# ADAU1452KCPZ.net
KiCad netlist of a schematic drawn in Altium Designer
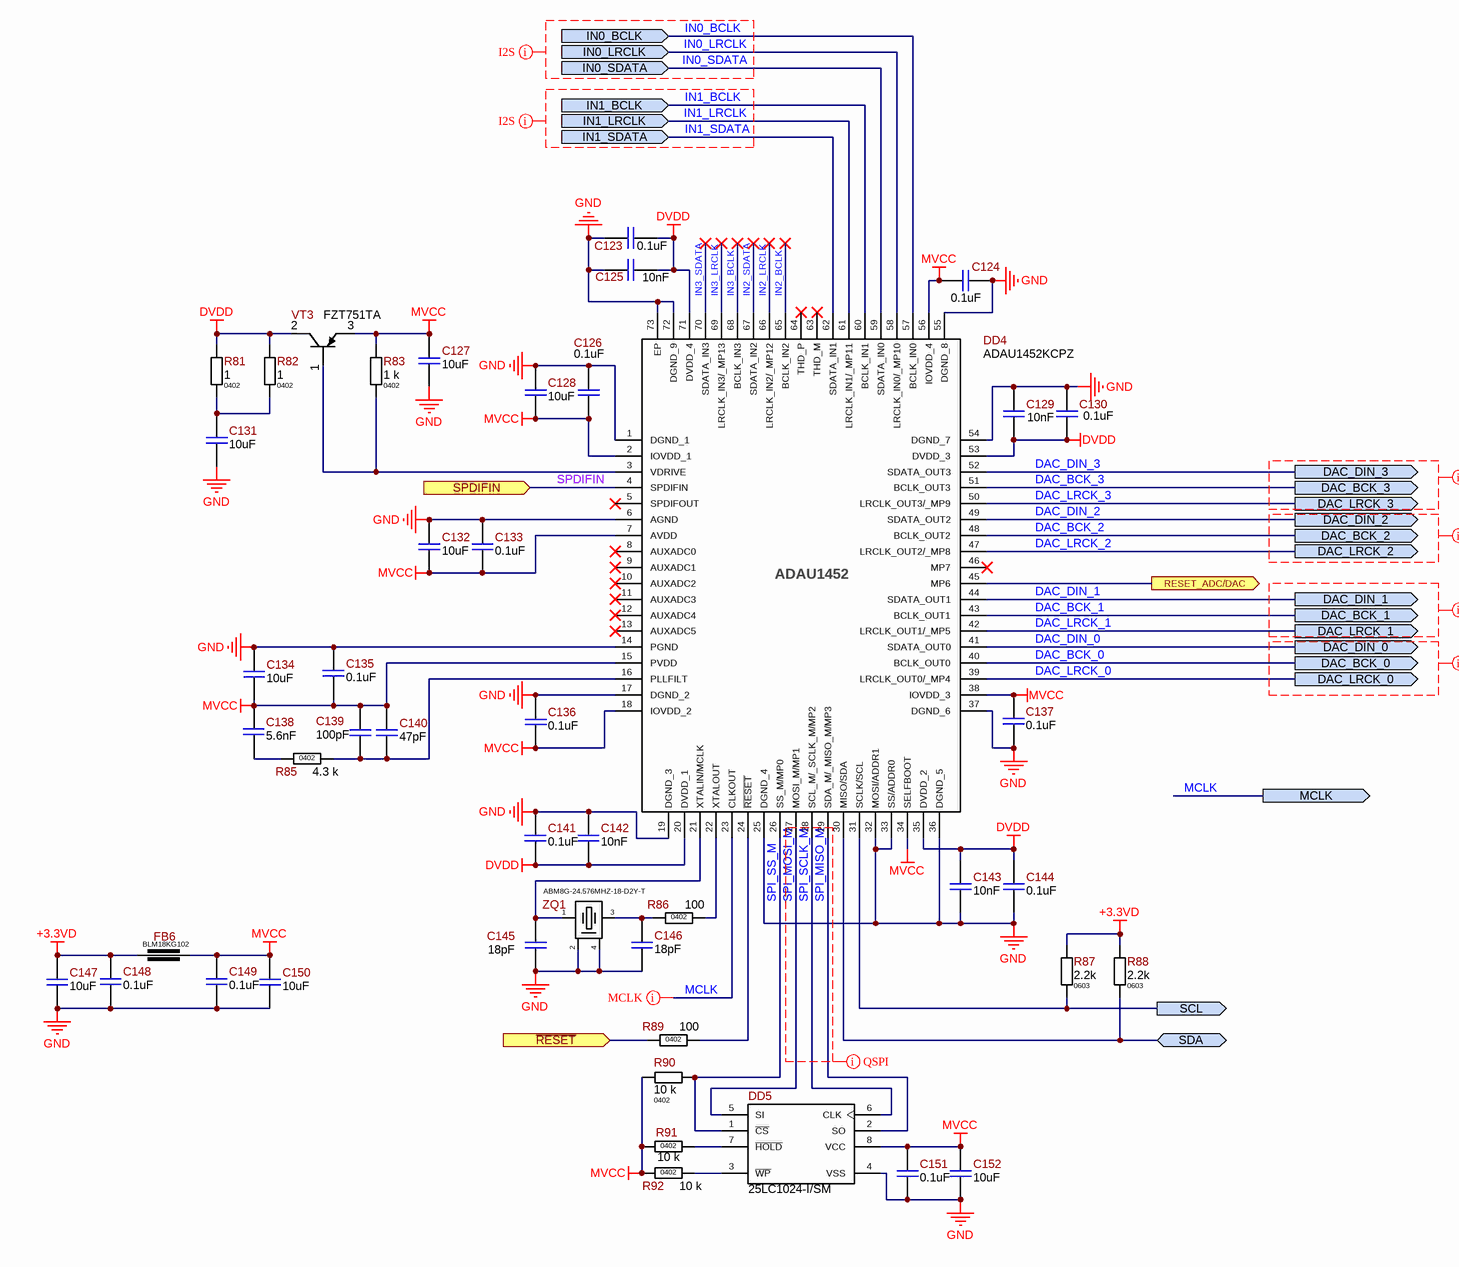
[diagram p0: ADAU1452KCPZ.SchDoc]

(export (version "E")
  (design (tool "Eeschema 10.0.6"))
  (components
    (comp (ref "C123")
      (value "0.1uF")
      (footprint "C0402(1005)")
      (description "CAP CER 0.1UF 25V X7R 0603")
      (fields (field (name "PART NUMBER") "0.1uF  25V C0403") (field (name "TOLERANCE") "±10%"))
      (libsource (lib "Database") (part "Capacitor_Ceramic"))
    )
    (comp (ref "C124")
      (value "0.1uF")
      (footprint "C0402(1005)")
      (description "CAP CER 0.1UF 25V X7R 0603")
      (fields (field (name "PART NUMBER") "0.1uF  25V C0403") (field (name "TOLERANCE") "±10%"))
      (libsource (lib "Database") (part "Capacitor_Ceramic"))
    )
    (comp (ref "C125")
      (value "10nF")
      (footprint "C0402(1005)")
      (description "CAP CER 10NF 50V NP0 0603")
      (fields (field (name "PART NUMBER") "10nF  50V C0402") (field (name "TOLERANCE") "±0.25pF"))
      (libsource (lib "Database") (part "Capacitor_Ceramic"))
    )
    (comp (ref "C126")
      (value "0.1uF")
      (footprint "C0402(1005)")
      (description "CAP CER 0.1UF 25V X7R 0603")
      (fields (field (name "PART NUMBER") "0.1uF  25V C0403") (field (name "TOLERANCE") "±10%"))
      (libsource (lib "Database") (part "Capacitor_Ceramic"))
    )
    (comp (ref "C127")
      (value "10uF")
      (footprint "C0402(1005)")
      (description "CAP CER 10UF 6.3V X6S 0402")
      (fields (field (name "PART NUMBER") "10uF  6.3V C0402") (field (name "TOLERANCE") "±20%"))
      (libsource (lib "Database") (part "Capacitor_Ceramic"))
    )
    (comp (ref "C128")
      (value "10uF")
      (footprint "C0402(1005)")
      (description "CAP CER 10UF 6.3V X6S 0402")
      (fields (field (name "PART NUMBER") "10uF  6.3V C0402") (field (name "TOLERANCE") "±20%"))
      (libsource (lib "Database") (part "Capacitor_Ceramic"))
    )
    (comp (ref "C129")
      (value "10nF")
      (footprint "C0402(1005)")
      (description "CAP CER 10NF 50V NP0 0603")
      (fields (field (name "PART NUMBER") "10nF  50V C0402") (field (name "TOLERANCE") "±0.25pF"))
      (libsource (lib "Database") (part "Capacitor_Ceramic"))
    )
    (comp (ref "C130")
      (value "0.1uF")
      (footprint "C0402(1005)")
      (description "CAP CER 0.1UF 25V X7R 0603")
      (fields (field (name "PART NUMBER") "0.1uF  25V C0403") (field (name "TOLERANCE") "±10%"))
      (libsource (lib "Database") (part "Capacitor_Ceramic"))
    )
    (comp (ref "C131")
      (value "10uF")
      (footprint "C0402(1005)")
      (description "CAP CER 10UF 6.3V X6S 0402")
      (fields (field (name "PART NUMBER") "10uF  6.3V C0402") (field (name "TOLERANCE") "±20%"))
      (libsource (lib "Database") (part "Capacitor_Ceramic"))
    )
    (comp (ref "C132")
      (value "10uF")
      (footprint "C0402(1005)")
      (description "CAP CER 10UF 6.3V X6S 0402")
      (fields (field (name "PART NUMBER") "10uF  6.3V C0402") (field (name "TOLERANCE") "±20%"))
      (libsource (lib "Database") (part "Capacitor_Ceramic"))
    )
    (comp (ref "C133")
      (value "0.1uF")
      (footprint "C0402(1005)")
      (description "CAP CER 0.1UF 25V X7R 0603")
      (fields (field (name "PART NUMBER") "0.1uF  25V C0403") (field (name "TOLERANCE") "±10%"))
      (libsource (lib "Database") (part "Capacitor_Ceramic"))
    )
    (comp (ref "C134")
      (value "10uF")
      (footprint "C0402(1005)")
      (description "CAP CER 10UF 6.3V X6S 0402")
      (fields (field (name "PART NUMBER") "10uF  6.3V C0402") (field (name "TOLERANCE") "±20%"))
      (libsource (lib "Database") (part "Capacitor_Ceramic"))
    )
    (comp (ref "C135")
      (value "0.1uF")
      (footprint "C0402(1005)")
      (description "CAP CER 0.1UF 25V X7R 0603")
      (fields (field (name "PART NUMBER") "0.1uF  25V C0403") (field (name "TOLERANCE") "±10%"))
      (libsource (lib "Database") (part "Capacitor_Ceramic"))
    )
    (comp (ref "C136")
      (value "0.1uF")
      (footprint "C0402(1005)")
      (description "CAP CER 0.1UF 25V X7R 0603")
      (fields (field (name "PART NUMBER") "0.1uF  25V C0403") (field (name "TOLERANCE") "±10%"))
      (libsource (lib "Database") (part "Capacitor_Ceramic"))
    )
    (comp (ref "C137")
      (value "0.1uF")
      (footprint "C0402(1005)")
      (description "CAP CER 0.1UF 25V X7R 0603")
      (fields (field (name "PART NUMBER") "0.1uF  25V C0403") (field (name "TOLERANCE") "±10%"))
      (libsource (lib "Database") (part "Capacitor_Ceramic"))
    )
    (comp (ref "C138")
      (value "5.6nF")
      (footprint "C0402(1005)")
      (description "CAP CER 5.6NF 50V NP0 0603")
      (fields (field (name "PART NUMBER") "5.6nF  50V C0402") (field (name "TOLERANCE") "±0.25pF"))
      (libsource (lib "Database") (part "Capacitor_Ceramic"))
    )
    (comp (ref "C139")
      (value "100pF")
      (footprint "C0402(1005)")
      (description "CAP CER 100PF 50V NP0 0603")
      (fields (field (name "PART NUMBER") "100pF  50V C0402") (field (name "TOLERANCE") "±0.25pF"))
      (libsource (lib "Database") (part "Capacitor_Ceramic"))
    )
    (comp (ref "C140")
      (value "47pF")
      (footprint "C0402(1005)")
      (description "CAP CER 47PF 50V NP0 0603")
      (fields (field (name "PART NUMBER") "47pF  50V C0402") (field (name "TOLERANCE") "±0.25pF"))
      (libsource (lib "Database") (part "Capacitor_Ceramic"))
    )
    (comp (ref "C141")
      (value "0.1uF")
      (footprint "C0402(1005)")
      (description "CAP CER 0.1UF 25V X7R 0603")
      (fields (field (name "PART NUMBER") "0.1uF  25V C0403") (field (name "TOLERANCE") "±10%"))
      (libsource (lib "Database") (part "Capacitor_Ceramic"))
    )
    (comp (ref "C142")
      (value "10nF")
      (footprint "C0402(1005)")
      (description "CAP CER 10NF 50V NP0 0603")
      (fields (field (name "PART NUMBER") "10nF  50V C0402") (field (name "TOLERANCE") "±0.25pF"))
      (libsource (lib "Database") (part "Capacitor_Ceramic"))
    )
    (comp (ref "C143")
      (value "10nF")
      (footprint "C0402(1005)")
      (description "CAP CER 10NF 50V NP0 0603")
      (fields (field (name "PART NUMBER") "10nF  50V C0402") (field (name "TOLERANCE") "±0.25pF"))
      (libsource (lib "Database") (part "Capacitor_Ceramic"))
    )
    (comp (ref "C144")
      (value "0.1uF")
      (footprint "C0402(1005)")
      (description "CAP CER 0.1UF 25V X7R 0603")
      (fields (field (name "PART NUMBER") "0.1uF  25V C0403") (field (name "TOLERANCE") "±10%"))
      (libsource (lib "Database") (part "Capacitor_Ceramic"))
    )
    (comp (ref "C145")
      (value "18pF")
      (footprint "C0402(1005)")
      (description "CAP CER 18PF 50V NP0 0603")
      (fields (field (name "PART NUMBER") "18pF  50V C0402") (field (name "TOLERANCE") "±0.25pF"))
      (libsource (lib "Database") (part "Capacitor_Ceramic"))
    )
    (comp (ref "C146")
      (value "18pF")
      (footprint "C0402(1005)")
      (description "CAP CER 18PF 50V NP0 0603")
      (fields (field (name "PART NUMBER") "18pF  50V C0402") (field (name "TOLERANCE") "±0.25pF"))
      (libsource (lib "Database") (part "Capacitor_Ceramic"))
    )
    (comp (ref "C147")
      (value "10uF")
      (footprint "C0402(1005)")
      (description "CAP CER 10UF 6.3V X6S 0402")
      (fields (field (name "PART NUMBER") "10uF  6.3V C0402") (field (name "TOLERANCE") "±20%"))
      (libsource (lib "Database") (part "Capacitor_Ceramic"))
    )
    (comp (ref "C148")
      (value "0.1uF")
      (footprint "C0402(1005)")
      (description "CAP CER 0.1UF 25V X7R 0603")
      (fields (field (name "PART NUMBER") "0.1uF  25V C0403") (field (name "TOLERANCE") "±10%"))
      (libsource (lib "Database") (part "Capacitor_Ceramic"))
    )
    (comp (ref "C149")
      (value "0.1uF")
      (footprint "C0402(1005)")
      (description "CAP CER 0.1UF 25V X7R 0603")
      (fields (field (name "PART NUMBER") "0.1uF  25V C0403") (field (name "TOLERANCE") "±10%"))
      (libsource (lib "Database") (part "Capacitor_Ceramic"))
    )
    (comp (ref "C150")
      (value "10uF")
      (footprint "C0402(1005)")
      (description "CAP CER 10UF 6.3V X6S 0402")
      (fields (field (name "PART NUMBER") "10uF  6.3V C0402") (field (name "TOLERANCE") "±20%"))
      (libsource (lib "Database") (part "Capacitor_Ceramic"))
    )
    (comp (ref "C151")
      (value "0.1uF")
      (footprint "C0402(1005)")
      (description "CAP CER 0.1UF 25V X7R 0603")
      (fields (field (name "PART NUMBER") "0.1uF  25V C0403") (field (name "TOLERANCE") "±10%"))
      (libsource (lib "Database") (part "Capacitor_Ceramic"))
    )
    (comp (ref "C152")
      (value "10uF")
      (footprint "C0402(1005)")
      (description "CAP CER 10UF 6.3V X6S 0402")
      (fields (field (name "PART NUMBER") "10uF  6.3V C0402") (field (name "TOLERANCE") "±20%"))
      (libsource (lib "Database") (part "Capacitor_Ceramic"))
    )
    (comp (ref "DD4")
      (value "ADAU1452KCPZ")
      (footprint "QFN50P1000X1000X100-73N-D")
      (description "300 MHZ 32BIT SIGMADSP AUDIO PRO")
      (fields (field (name "MANUFACTURER") "Analog Devices Inc."))
      (libsource (lib "Database") (part "ADAU1452KCPZ"))
    )
    (comp (ref "DD5")
      (value "25LC1024-I/SM")
      (footprint "SOIC8")
      (description "EEPROM Memory IC 1Mbit SPI 20 MHz 8-SOIJ")
      (fields (field (name "MANUFACTURER") "Microchip Technology"))
      (libsource (lib "Database") (part "W25Q32"))
    )
    (comp (ref "FB6")
      (value "BLM18KG102")
      (footprint "BLM18(0603)")
      (description "FERRITE BEAD 1 KOHM 0603 1LN")
      (fields
        (field (name "TOLERANCE") "±25%")
        (field (name "MANUFACTURER") "Murata Electronics North America")
      )
      (libsource (lib "Database") (part "FB"))
    )
    (comp (ref "R81")
      (value "1")
      (footprint "R0402")
      (description "RES SMD 1 OHM  ±1% 1/16W 0402")
      (fields
        (field (name "PACKAGE/CASE") "0402")
        (field (name "PART NUMBER") "1  R0402")
        (field (name "TOLERANCE") "±1%")
      )
      (libsource (lib "Database") (part "R0402"))
    )
    (comp (ref "R82")
      (value "1")
      (footprint "R0402")
      (description "RES SMD 1 OHM  ±1% 1/16W 0402")
      (fields
        (field (name "PACKAGE/CASE") "0402")
        (field (name "PART NUMBER") "1  R0402")
        (field (name "TOLERANCE") "±1%")
      )
      (libsource (lib "Database") (part "R0402"))
    )
    (comp (ref "R83")
      (value "1 k")
      (footprint "R0402")
      (description "RES SMD 1 k OHM  ±1% 1/16W 0402")
      (fields
        (field (name "PACKAGE/CASE") "0402")
        (field (name "PART NUMBER") "1 k  R0402")
        (field (name "TOLERANCE") "±1%")
      )
      (libsource (lib "Database") (part "R0402"))
    )
    (comp (ref "R85")
      (value "4.3 k")
      (footprint "R0402")
      (description "RES SMD 4.3 k OHM  ±1% 1/16W 0402")
      (fields
        (field (name "PACKAGE/CASE") "0402")
        (field (name "PART NUMBER") "4.3 k  R0402")
        (field (name "TOLERANCE") "±1%")
      )
      (libsource (lib "Database") (part "R0402"))
    )
    (comp (ref "R86")
      (value "100")
      (footprint "R0402")
      (description "RES SMD 100 OHM  ±1% 1/16W 0402")
      (fields
        (field (name "PACKAGE/CASE") "0402")
        (field (name "PART NUMBER") "100  R0402")
        (field (name "TOLERANCE") "±1%")
      )
      (libsource (lib "Database") (part "R0402"))
    )
    (comp (ref "R87")
      (value "2.2k")
      (footprint "R0603")
      (description "RES SMD 10 k OHM  ±1% 1/10W 0603")
      (fields
        (field (name "PACKAGE/CASE") "0603")
        (field (name "PART NUMBER") "10 k  R0603")
        (field (name "TOLERANCE") "±1%")
      )
      (libsource (lib "Database") (part "R0603"))
    )
    (comp (ref "R88")
      (value "2.2k")
      (footprint "R0603")
      (description "RES SMD 10 k OHM  ±1% 1/10W 0603")
      (fields
        (field (name "PACKAGE/CASE") "0603")
        (field (name "PART NUMBER") "10 k  R0603")
        (field (name "TOLERANCE") "±1%")
      )
      (libsource (lib "Database") (part "R0603"))
    )
    (comp (ref "R89")
      (value "100")
      (footprint "R0402")
      (description "RES SMD 100 OHM  ±1% 1/16W 0402")
      (fields
        (field (name "PACKAGE/CASE") "0402")
        (field (name "PART NUMBER") "100  R0402")
        (field (name "TOLERANCE") "±1%")
      )
      (libsource (lib "Database") (part "R0402"))
    )
    (comp (ref "R90")
      (value "10 k")
      (footprint "R0402")
      (description "RES SMD 10 k OHM  ±1% 1/16W 0402")
      (fields
        (field (name "PACKAGE/CASE") "0402")
        (field (name "PART NUMBER") "10 k  R0402")
        (field (name "TOLERANCE") "±1%")
      )
      (libsource (lib "Database") (part "R0402"))
    )
    (comp (ref "R91")
      (value "10 k")
      (footprint "R0402")
      (description "RES SMD 10 k OHM  ±1% 1/16W 0402")
      (fields
        (field (name "PACKAGE/CASE") "0402")
        (field (name "PART NUMBER") "10 k  R0402")
        (field (name "TOLERANCE") "±1%")
      )
      (libsource (lib "Database") (part "R0402"))
    )
    (comp (ref "R92")
      (value "10 k")
      (footprint "R0402")
      (description "RES SMD 10 k OHM  ±1% 1/16W 0402")
      (fields
        (field (name "PACKAGE/CASE") "0402")
        (field (name "PART NUMBER") "10 k  R0402")
        (field (name "TOLERANCE") "±1%")
      )
      (libsource (lib "Database") (part "R0402"))
    )
    (comp (ref "VT3")
      (value "FZT751TA")
      (footprint "SOT-223")
      (description "Bipolar (BJT) Transistor PNP 60 V 3 A 140MHz 2 W Surface Mount SOT-223-3")
      (fields (field (name "MANUFACTURER") "Diodes Incorporated"))
      (libsource (lib "Database") (part "FZT751TA"))
    )
    (comp (ref "ZQ1")
      (value "ABM8G-24.576MHZ-18-D2Y-T")
      (footprint "ABM8")
      (description "CRYSTAL 24.5760MHZ 18PF SMD")
      (fields (field (name "TOLERANCE") "±20ppm") (field (name "MANUFACTURER") "Abracon LLC"))
      (libsource (lib "Database") (part "Crystals_2"))
    )
  )
  (nets
    (net (code "1") (name "+3.3VD") (class "Default")
      (node (ref "C147") (pin "2") (pinfunction "2_2") (pintype "passive"))
      (node (ref "C148") (pin "1") (pinfunction "1_1") (pintype "passive"))
      (node (ref "FB6") (pin "1") (pintype "passive"))
      (node (ref "R87") (pin "1") (pinfunction "1_1") (pintype "passive"))
      (node (ref "R88") (pin "1") (pinfunction "1_1") (pintype "passive"))
    )
    (net (code "2") (name "/DAC_BCK_0") (class "Default")
      (node (ref "DD4") (pin "40") (pinfunction "BCLK_OUT0_40") (pintype "passive"))
    )
    (net (code "3") (name "/DAC_BCK_1") (class "Default")
      (node (ref "DD4") (pin "43") (pinfunction "BCLK_OUT1_43") (pintype "passive"))
    )
    (net (code "4") (name "/DAC_BCK_2") (class "Default")
      (node (ref "DD4") (pin "48") (pinfunction "BCLK_OUT2_48") (pintype "passive"))
    )
    (net (code "5") (name "/DAC_BCK_3") (class "Default")
      (node (ref "DD4") (pin "51") (pinfunction "BCLK_OUT3_51") (pintype "passive"))
    )
    (net (code "6") (name "/DAC_DIN_0") (class "Default")
      (node (ref "DD4") (pin "41") (pinfunction "SDATA_OUT0_41") (pintype "passive"))
    )
    (net (code "7") (name "/DAC_DIN_1") (class "Default")
      (node (ref "DD4") (pin "44") (pinfunction "SDATA_OUT1_44") (pintype "passive"))
    )
    (net (code "8") (name "/DAC_DIN_2") (class "Default")
      (node (ref "DD4") (pin "49") (pinfunction "SDATA_OUT2_49") (pintype "passive"))
    )
    (net (code "9") (name "/DAC_DIN_3") (class "Default")
      (node (ref "DD4") (pin "52") (pinfunction "SDATA_OUT3_52") (pintype "passive"))
    )
    (net (code "10") (name "/DAC_LRCK_0") (class "Default")
      (node (ref "DD4") (pin "39") (pinfunction "LRCLK_OUT0/_MP4_39") (pintype "passive"))
    )
    (net (code "11") (name "/DAC_LRCK_1") (class "Default")
      (node (ref "DD4") (pin "42") (pinfunction "LRCLK_OUT1/_MP5_42") (pintype "passive"))
    )
    (net (code "12") (name "/DAC_LRCK_2") (class "Default")
      (node (ref "DD4") (pin "47") (pinfunction "LRCLK_OUT2/_MP8_47") (pintype "passive"))
    )
    (net (code "13") (name "/DAC_LRCK_3") (class "Default")
      (node (ref "DD4") (pin "50") (pinfunction "LRCLK_OUT3/_MP9_50") (pintype "passive"))
    )
    (net (code "14") (name "/IN0_BCLK") (class "Default")
      (node (ref "DD4") (pin "57") (pinfunction "BCLK_IN0_57") (pintype "passive"))
    )
    (net (code "15") (name "/IN0_LRCLK") (class "Default")
      (node (ref "DD4") (pin "58") (pinfunction "LRCLK_IN0/_MP10_58") (pintype "passive"))
    )
    (net (code "16") (name "/IN0_SDATA") (class "Default")
      (node (ref "DD4") (pin "59") (pinfunction "SDATA_IN0_59") (pintype "passive"))
    )
    (net (code "17") (name "/IN1_BCLK") (class "Default")
      (node (ref "DD4") (pin "60") (pinfunction "BCLK_IN1_60") (pintype "passive"))
    )
    (net (code "18") (name "/IN1_LRCLK") (class "Default")
      (node (ref "DD4") (pin "61") (pinfunction "LRCLK_IN1/_MP11_61") (pintype "passive"))
    )
    (net (code "19") (name "/IN1_SDATA") (class "Default")
      (node (ref "DD4") (pin "62") (pinfunction "SDATA_IN1_62") (pintype "passive"))
    )
    (net (code "20") (name "/IN2_BCLK") (class "Default")
      (node (ref "DD4") (pin "65") (pinfunction "BCLK_IN2_65") (pintype "passive+no_connect"))
    )
    (net (code "21") (name "/IN2_LRCLK") (class "Default")
      (node (ref "DD4") (pin "66") (pinfunction "LRCLK_IN2/_MP12_66") (pintype "passive+no_connect"))
    )
    (net (code "22") (name "/IN2_SDATA") (class "Default")
      (node (ref "DD4") (pin "67") (pinfunction "SDATA_IN2_67") (pintype "passive+no_connect"))
    )
    (net (code "23") (name "/IN3_BCLK") (class "Default")
      (node (ref "DD4") (pin "68") (pinfunction "BCLK_IN3_68") (pintype "passive+no_connect"))
    )
    (net (code "24") (name "/IN3_LRCLK") (class "Default")
      (node (ref "DD4") (pin "69") (pinfunction "LRCLK_IN3/_MP13_69") (pintype "passive+no_connect"))
    )
    (net (code "25") (name "/IN3_SDATA") (class "Default")
      (node (ref "DD4") (pin "70") (pinfunction "SDATA_IN3_70") (pintype "passive+no_connect"))
    )
    (net (code "26") (name "/MCLK") (class "Default")
      (node (ref "DD4") (pin "23") (pinfunction "CLKOUT_23") (pintype "passive"))
    )
    (net (code "27") (name "/RESET_ADC{slash}DAC") (class "Default")
      (node (ref "DD4") (pin "45") (pinfunction "MP6_45") (pintype "passive"))
    )
    (net (code "28") (name "/SCL") (class "Default")
      (node (ref "DD4") (pin "31") (pinfunction "SCLK/SCL_31") (pintype "passive"))
      (node (ref "R87") (pin "2") (pinfunction "2_2") (pintype "passive"))
    )
    (net (code "29") (name "/SDA") (class "Default")
      (node (ref "DD4") (pin "30") (pinfunction "MISO/SDA_30") (pintype "passive"))
      (node (ref "R88") (pin "2") (pinfunction "2_2") (pintype "passive"))
    )
    (net (code "30") (name "/SPDIFIN") (class "Default")
      (node (ref "DD4") (pin "4") (pinfunction "SPDIFIN_4") (pintype "passive"))
    )
    (net (code "31") (name "/SPI_MISO_M") (class "Default")
      (node (ref "DD4") (pin "29") (pinfunction "SDA_M/_MISO_M/MP3_29") (pintype "passive"))
      (node (ref "DD5") (pin "2") (pinfunction "SO_2") (pintype "passive"))
    )
    (net (code "32") (name "/SPI_MOSI_M") (class "Default")
      (node (ref "DD4") (pin "27") (pinfunction "MOSI_M/MP1_27") (pintype "passive"))
      (node (ref "DD5") (pin "5") (pinfunction "SI_5") (pintype "passive"))
    )
    (net (code "33") (name "/SPI_SCLK_M") (class "Default")
      (node (ref "DD4") (pin "28") (pinfunction "SCL_M/_SCLK_M/MP2_28") (pintype "passive"))
      (node (ref "DD5") (pin "6") (pinfunction "CLK_6") (pintype "passive"))
    )
    (net (code "34") (name "/SPI_SS_M") (class "Default")
      (node (ref "DD4") (pin "26") (pinfunction "SS_M/MP0_26") (pintype "passive"))
      (node (ref "DD5") (pin "1") (pinfunction "~{CS}_1") (pintype "passive"))
      (node (ref "R90") (pin "2") (pinfunction "2_2") (pintype "passive"))
    )
    (net (code "35") (name "/~{RESET}") (class "Default")
      (node (ref "R89") (pin "2") (pinfunction "2_2") (pintype "passive"))
    )
    (net (code "36") (name "DVDD") (class "Default")
      (node (ref "C123") (pin "2") (pinfunction "2_2") (pintype "passive"))
      (node (ref "C125") (pin "2") (pinfunction "2_2") (pintype "passive"))
      (node (ref "C129") (pin "1") (pinfunction "1_1") (pintype "passive"))
      (node (ref "C130") (pin "1") (pinfunction "1_1") (pintype "passive"))
      (node (ref "C141") (pin "2") (pinfunction "2_2") (pintype "passive"))
      (node (ref "C142") (pin "2") (pinfunction "2_2") (pintype "passive"))
      (node (ref "C143") (pin "2") (pinfunction "2_2") (pintype "passive"))
      (node (ref "C144") (pin "2") (pinfunction "2_2") (pintype "passive"))
      (node (ref "DD4") (pin "20") (pinfunction "DVDD_1_20") (pintype "passive"))
      (node (ref "DD4") (pin "35") (pinfunction "DVDD_2_35") (pintype "passive"))
      (node (ref "DD4") (pin "53") (pinfunction "DVDD_3_53") (pintype "passive"))
      (node (ref "DD4") (pin "71") (pinfunction "DVDD_4_71") (pintype "passive"))
      (node (ref "R81") (pin "1") (pinfunction "1_1") (pintype "passive"))
      (node (ref "R82") (pin "1") (pinfunction "1_1") (pintype "passive"))
      (node (ref "VT3") (pin "2") (pinfunction "C_2") (pintype "passive"))
    )
    (net (code "37") (name "GND") (class "Default")
      (node (ref "C123") (pin "1") (pinfunction "1_1") (pintype "passive"))
      (node (ref "C124") (pin "2") (pinfunction "2_2") (pintype "passive"))
      (node (ref "C125") (pin "1") (pinfunction "1_1") (pintype "passive"))
      (node (ref "C126") (pin "2") (pinfunction "2_2") (pintype "passive"))
      (node (ref "C127") (pin "1") (pinfunction "1_1") (pintype "passive"))
      (node (ref "C128") (pin "2") (pinfunction "2_2") (pintype "passive"))
      (node (ref "C129") (pin "2") (pinfunction "2_2") (pintype "passive"))
      (node (ref "C130") (pin "2") (pinfunction "2_2") (pintype "passive"))
      (node (ref "C131") (pin "1") (pinfunction "1_1") (pintype "passive"))
      (node (ref "C132") (pin "2") (pinfunction "2_2") (pintype "passive"))
      (node (ref "C133") (pin "2") (pinfunction "2_2") (pintype "passive"))
      (node (ref "C134") (pin "2") (pinfunction "2_2") (pintype "passive"))
      (node (ref "C135") (pin "1") (pinfunction "1_1") (pintype "passive"))
      (node (ref "C136") (pin "2") (pinfunction "2_2") (pintype "passive"))
      (node (ref "C137") (pin "2") (pinfunction "2_2") (pintype "passive"))
      (node (ref "C141") (pin "1") (pinfunction "1_1") (pintype "passive"))
      (node (ref "C142") (pin "1") (pinfunction "1_1") (pintype "passive"))
      (node (ref "C143") (pin "1") (pinfunction "1_1") (pintype "passive"))
      (node (ref "C144") (pin "1") (pinfunction "1_1") (pintype "passive"))
      (node (ref "C145") (pin "1") (pinfunction "1_1") (pintype "passive"))
      (node (ref "C146") (pin "1") (pinfunction "1_1") (pintype "passive"))
      (node (ref "C147") (pin "1") (pinfunction "1_1") (pintype "passive"))
      (node (ref "C148") (pin "2") (pinfunction "2_2") (pintype "passive"))
      (node (ref "C149") (pin "2") (pinfunction "2_2") (pintype "passive"))
      (node (ref "C150") (pin "1") (pinfunction "1_1") (pintype "passive"))
      (node (ref "C151") (pin "1") (pinfunction "1_1") (pintype "passive"))
      (node (ref "C152") (pin "1") (pinfunction "1_1") (pintype "passive"))
      (node (ref "DD4") (pin "1") (pinfunction "DGND_1_1") (pintype "passive"))
      (node (ref "DD4") (pin "14") (pinfunction "PGND_14") (pintype "passive"))
      (node (ref "DD4") (pin "17") (pinfunction "DGND_2_17") (pintype "passive"))
      (node (ref "DD4") (pin "19") (pinfunction "DGND_3_19") (pintype "passive"))
      (node (ref "DD4") (pin "25") (pinfunction "DGND_4_25") (pintype "passive"))
      (node (ref "DD4") (pin "32") (pinfunction "MOSI/ADDR1_32") (pintype "passive"))
      (node (ref "DD4") (pin "33") (pinfunction "SS/ADDR0_33") (pintype "passive"))
      (node (ref "DD4") (pin "36") (pinfunction "DGND_5_36") (pintype "passive"))
      (node (ref "DD4") (pin "37") (pinfunction "DGND_6_37") (pintype "passive"))
      (node (ref "DD4") (pin "54") (pinfunction "DGND_7_54") (pintype "passive"))
      (node (ref "DD4") (pin "55") (pinfunction "DGND_8_55") (pintype "passive"))
      (node (ref "DD4") (pin "6") (pinfunction "AGND_6") (pintype "passive"))
      (node (ref "DD4") (pin "72") (pinfunction "DGND_9_72") (pintype "passive"))
      (node (ref "DD4") (pin "73") (pinfunction "EP_73") (pintype "passive"))
      (node (ref "DD5") (pin "4") (pinfunction "VSS_4") (pintype "passive"))
      (node (ref "ZQ1") (pin "2") (pinfunction "Body_2") (pintype "passive"))
      (node (ref "ZQ1") (pin "4") (pinfunction "Body_4") (pintype "passive"))
    )
    (net (code "38") (name "MVCC") (class "Default")
      (node (ref "C124") (pin "1") (pinfunction "1_1") (pintype "passive"))
      (node (ref "C126") (pin "1") (pinfunction "1_1") (pintype "passive"))
      (node (ref "C127") (pin "2") (pinfunction "2_2") (pintype "passive"))
      (node (ref "C128") (pin "1") (pinfunction "1_1") (pintype "passive"))
      (node (ref "C132") (pin "1") (pinfunction "1_1") (pintype "passive"))
      (node (ref "C133") (pin "1") (pinfunction "1_1") (pintype "passive"))
      (node (ref "C134") (pin "1") (pinfunction "1_1") (pintype "passive"))
      (node (ref "C135") (pin "2") (pinfunction "2_2") (pintype "passive"))
      (node (ref "C136") (pin "1") (pinfunction "1_1") (pintype "passive"))
      (node (ref "C137") (pin "1") (pinfunction "1_1") (pintype "passive"))
      (node (ref "C138") (pin "1") (pinfunction "1_1") (pintype "passive"))
      (node (ref "C139") (pin "2") (pinfunction "2_2") (pintype "passive"))
      (node (ref "C140") (pin "2") (pinfunction "2_2") (pintype "passive"))
      (node (ref "C149") (pin "1") (pinfunction "1_1") (pintype "passive"))
      (node (ref "C150") (pin "2") (pinfunction "2_2") (pintype "passive"))
      (node (ref "C151") (pin "2") (pinfunction "2_2") (pintype "passive"))
      (node (ref "C152") (pin "2") (pinfunction "2_2") (pintype "passive"))
      (node (ref "DD4") (pin "15") (pinfunction "PVDD_15") (pintype "passive"))
      (node (ref "DD4") (pin "18") (pinfunction "IOVDD_2_18") (pintype "passive"))
      (node (ref "DD4") (pin "2") (pinfunction "IOVDD_1_2") (pintype "passive"))
      (node (ref "DD4") (pin "34") (pinfunction "SELFBOOT_34") (pintype "passive"))
      (node (ref "DD4") (pin "38") (pinfunction "IOVDD_3_38") (pintype "passive"))
      (node (ref "DD4") (pin "56") (pinfunction "IOVDD_4_56") (pintype "passive"))
      (node (ref "DD4") (pin "7") (pinfunction "AVDD_7") (pintype "passive"))
      (node (ref "DD5") (pin "8") (pinfunction "VCC_8") (pintype "passive"))
      (node (ref "FB6") (pin "2") (pintype "passive"))
      (node (ref "R83") (pin "1") (pinfunction "1_1") (pintype "passive"))
      (node (ref "R90") (pin "1") (pinfunction "1_1") (pintype "passive"))
      (node (ref "R91") (pin "2") (pinfunction "2_2") (pintype "passive"))
      (node (ref "R92") (pin "2") (pinfunction "2_2") (pintype "passive"))
      (node (ref "VT3") (pin "3") (pinfunction "E_3") (pintype "passive"))
    )
    (net (code "39") (name "Net-(C131-Pad2)") (class "Default")
      (node (ref "C131") (pin "2") (pinfunction "2_2") (pintype "passive"))
      (node (ref "R81") (pin "2") (pinfunction "2_2") (pintype "passive"))
      (node (ref "R82") (pin "2") (pinfunction "2_2") (pintype "passive"))
    )
    (net (code "40") (name "Net-(C138-Pad2)") (class "Default")
      (node (ref "C138") (pin "2") (pinfunction "2_2") (pintype "passive"))
      (node (ref "R85") (pin "2") (pinfunction "2_2") (pintype "passive"))
    )
    (net (code "41") (name "Net-(DD4-PLLFILT)") (class "Default")
      (node (ref "C139") (pin "1") (pinfunction "1_1") (pintype "passive"))
      (node (ref "C140") (pin "1") (pinfunction "1_1") (pintype "passive"))
      (node (ref "DD4") (pin "16") (pinfunction "PLLFILT_16") (pintype "passive"))
      (node (ref "R85") (pin "1") (pinfunction "1_1") (pintype "passive"))
    )
    (net (code "42") (name "Net-(DD4-VDRIVE)") (class "Default")
      (node (ref "DD4") (pin "3") (pinfunction "VDRIVE_3") (pintype "passive"))
      (node (ref "R83") (pin "2") (pinfunction "2_2") (pintype "passive"))
      (node (ref "VT3") (pin "1") (pinfunction "B_1") (pintype "passive"))
    )
    (net (code "43") (name "Net-(DD4-XTALIN{slash}MCLK)") (class "Default")
      (node (ref "C145") (pin "2") (pinfunction "2_2") (pintype "passive"))
      (node (ref "DD4") (pin "21") (pinfunction "XTALIN/MCLK_21") (pintype "passive"))
      (node (ref "ZQ1") (pin "1") (pinfunction "X1_1") (pintype "passive"))
    )
    (net (code "44") (name "Net-(DD4-XTALOUT)") (class "Default")
      (node (ref "DD4") (pin "22") (pinfunction "XTALOUT_22") (pintype "passive"))
      (node (ref "R86") (pin "1") (pinfunction "1_1") (pintype "passive"))
    )
    (net (code "45") (name "Net-(DD4-~{RESET})") (class "Default")
      (node (ref "DD4") (pin "24") (pinfunction "~{RESET}_24") (pintype "passive"))
      (node (ref "R89") (pin "1") (pinfunction "1_1") (pintype "passive"))
    )
    (net (code "46") (name "Net-(DD5-~{HOLD})") (class "Default")
      (node (ref "DD5") (pin "7") (pinfunction "~{HOLD}_7") (pintype "passive"))
      (node (ref "R91") (pin "1") (pinfunction "1_1") (pintype "passive"))
    )
    (net (code "47") (name "Net-(DD5-~{WP})") (class "Default")
      (node (ref "DD5") (pin "3") (pinfunction "~{WP}_3") (pintype "passive"))
      (node (ref "R92") (pin "1") (pinfunction "1_1") (pintype "passive"))
    )
    (net (code "48") (name "Net-(ZQ1-X2)") (class "Default")
      (node (ref "C146") (pin "2") (pinfunction "2_2") (pintype "passive"))
      (node (ref "R86") (pin "2") (pinfunction "2_2") (pintype "passive"))
      (node (ref "ZQ1") (pin "3") (pinfunction "X2_3") (pintype "passive"))
    )
    (net (code "49") (name "unconnected-(DD4-AUXADC0-Pad8)") (class "Default")
      (node (ref "DD4") (pin "8") (pinfunction "AUXADC0_8") (pintype "passive+no_connect"))
    )
    (net (code "50") (name "unconnected-(DD4-AUXADC1-Pad9)") (class "Default")
      (node (ref "DD4") (pin "9") (pinfunction "AUXADC1_9") (pintype "passive+no_connect"))
    )
    (net (code "51") (name "unconnected-(DD4-AUXADC2-Pad10)") (class "Default")
      (node (ref "DD4") (pin "10") (pinfunction "AUXADC2_10") (pintype "passive+no_connect"))
    )
    (net (code "52") (name "unconnected-(DD4-AUXADC3-Pad11)") (class "Default")
      (node (ref "DD4") (pin "11") (pinfunction "AUXADC3_11") (pintype "passive+no_connect"))
    )
    (net (code "53") (name "unconnected-(DD4-AUXADC4-Pad12)") (class "Default")
      (node (ref "DD4") (pin "12") (pinfunction "AUXADC4_12") (pintype "passive+no_connect"))
    )
    (net (code "54") (name "unconnected-(DD4-AUXADC5-Pad13)") (class "Default")
      (node (ref "DD4") (pin "13") (pinfunction "AUXADC5_13") (pintype "passive+no_connect"))
    )
    (net (code "55") (name "unconnected-(DD4-MP7-Pad46)") (class "Default")
      (node (ref "DD4") (pin "46") (pinfunction "MP7_46") (pintype "passive+no_connect"))
    )
    (net (code "56") (name "unconnected-(DD4-SPDIFOUT-Pad5)") (class "Default")
      (node (ref "DD4") (pin "5") (pinfunction "SPDIFOUT_5") (pintype "passive+no_connect"))
    )
    (net (code "57") (name "unconnected-(DD4-THD_M-Pad63)") (class "Default")
      (node (ref "DD4") (pin "63") (pinfunction "THD_M_63") (pintype "passive+no_connect"))
    )
    (net (code "58") (name "unconnected-(DD4-THD_P-Pad64)") (class "Default")
      (node (ref "DD4") (pin "64") (pinfunction "THD_P_64") (pintype "passive+no_connect"))
    )
  )
)
